# state_indicator.net
KiCad netlist of a schematic drawn in Altium Designer
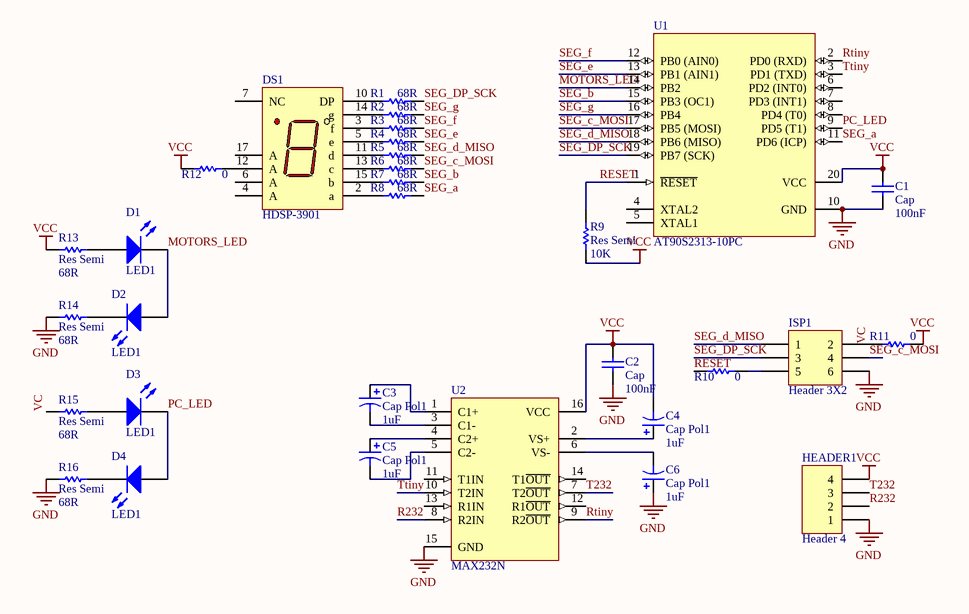
[diagram p0: state indicator.SchDoc]

(export (version "E")
  (design (tool "Eeschema 10.0.6"))
  (components
    (comp (ref "C1")
      (value "Cap")
      (footprint "CAPR5.08-7.8x3.2")
      (description "Capacitor")
      (fields (field (name "ALTIUM_VALUE") "100nF") (field (name "PUBLISHER") "Altium Limited"))
      (libsource (lib "Miscellaneous Devices") (part "Cap"))
    )
    (comp (ref "C2")
      (value "Cap")
      (footprint "CAPR5.08-7.8x3.2")
      (description "Capacitor")
      (fields (field (name "ALTIUM_VALUE") "100nF") (field (name "PUBLISHER") "Altium Limited"))
      (libsource (lib "Miscellaneous Devices") (part "Cap"))
    )
    (comp (ref "C3")
      (value "Cap Pol1")
      (footprint "CAPPR2-5x6.8")
      (description "Polarized Capacitor (Radial)")
      (fields (field (name "ALTIUM_VALUE") "1uF") (field (name "PUBLISHER") "Altium Limited"))
      (libsource (lib "state indicator") (part "Cap Pol1"))
    )
    (comp (ref "C4")
      (value "Cap Pol1")
      (footprint "CAPPR2-5x6.8")
      (description "Polarized Capacitor (Radial)")
      (fields (field (name "ALTIUM_VALUE") "1uF") (field (name "PUBLISHER") "Altium Limited"))
      (libsource (lib "state indicator") (part "Cap Pol1"))
    )
    (comp (ref "C5")
      (value "Cap Pol1")
      (footprint "CAPPR2-5x6.8")
      (description "Polarized Capacitor (Radial)")
      (fields (field (name "ALTIUM_VALUE") "1uF") (field (name "PUBLISHER") "Altium Limited"))
      (libsource (lib "state indicator") (part "Cap Pol1"))
    )
    (comp (ref "C6")
      (value "Cap Pol1")
      (footprint "CAPPR2-5x6.8")
      (description "Polarized Capacitor (Radial)")
      (fields (field (name "ALTIUM_VALUE") "1uF") (field (name "PUBLISHER") "Altium Limited"))
      (libsource (lib "state indicator") (part "Cap Pol1"))
    )
    (comp (ref "D1")
      (value "LED1")
      (footprint "LED-1")
      (description "Typical RED GaAs LED")
      (fields (field (name "PUBLISHER") "Altium Limited"))
      (libsource (lib "Miscellaneous Devices") (part "LED1"))
    )
    (comp (ref "D2")
      (value "LED1")
      (footprint "LED-1")
      (description "Typical RED GaAs LED")
      (fields (field (name "PUBLISHER") "Altium Limited"))
      (libsource (lib "Miscellaneous Devices") (part "LED1"))
    )
    (comp (ref "D3")
      (value "LED1")
      (footprint "LED-1")
      (description "Typical RED GaAs LED")
      (fields (field (name "PUBLISHER") "Altium Limited"))
      (libsource (lib "Miscellaneous Devices") (part "LED1"))
    )
    (comp (ref "D4")
      (value "LED1")
      (footprint "LED-1")
      (description "Typical RED GaAs LED")
      (fields (field (name "PUBLISHER") "Altium Limited"))
      (libsource (lib "Miscellaneous Devices") (part "LED1"))
    )
    (comp (ref "DS1")
      (value "HDSP-3901")
      (footprint "N-13")
      (description "20.32 mm Gray Package HER 7-Segment Display: CA, RH DP")
      (fields (field (name "PUBLISHER") "Altium Limited"))
      (libsource (lib "Agilent LED Display 7-Segment, 1-Digit") (part "HDSP-3901"))
    )
    (comp (ref "HEADER1")
      (value "Header 4")
      (footprint "HDR1X4")
      (description "Header, 4-Pin")
      (fields (field (name "PUBLISHER") "Altium Limited"))
      (libsource (lib "stabilizer") (part "Header 4"))
    )
    (comp (ref "ISP1")
      (value "Header 3X2")
      (footprint "stabilizer:HDR2X3")
      (description "Header, 3-Pin, Dual row")
      (fields (field (name "PUBLISHER") "Altium Limited"))
      (libsource (lib "Miscellaneous Connectors") (part "Header 3X2"))
    )
    (comp (ref "R1")
      (value "68R")
      (footprint "RES10-7.8X2.8")
      (description "Semiconductor Resistor")
      (fields (field (name "Comment") "es Semi") (field (name "PUBLISHER") "Altium Limited"))
      (libsource (lib "state indicator") (part "Res Semi"))
    )
    (comp (ref "R2")
      (value "68R")
      (footprint "RES10-7.8X2.8")
      (description "Semiconductor Resistor")
      (fields (field (name "Comment") "Res Semi") (field (name "PUBLISHER") "Altium Limited"))
      (libsource (lib "state indicator") (part "Res Semi"))
    )
    (comp (ref "R3")
      (value "68R")
      (footprint "RES10-7.8X2.8")
      (description "Semiconductor Resistor")
      (fields (field (name "Comment") "Res Semi") (field (name "PUBLISHER") "Altium Limited"))
      (libsource (lib "state indicator") (part "Res Semi"))
    )
    (comp (ref "R4")
      (value "68R")
      (footprint "RES10-7.8X2.8")
      (description "Semiconductor Resistor")
      (fields (field (name "Comment") "Res Semi") (field (name "PUBLISHER") "Altium Limited"))
      (libsource (lib "state indicator") (part "Res Semi"))
    )
    (comp (ref "R5")
      (value "68R")
      (footprint "RES10-7.8X2.8")
      (description "Semiconductor Resistor")
      (fields (field (name "Comment") "Res Semi") (field (name "PUBLISHER") "Altium Limited"))
      (libsource (lib "state indicator") (part "Res Semi"))
    )
    (comp (ref "R6")
      (value "68R")
      (footprint "RES10-7.8X2.8")
      (description "Semiconductor Resistor")
      (fields (field (name "Comment") "Res Semi") (field (name "PUBLISHER") "Altium Limited"))
      (libsource (lib "state indicator") (part "Res Semi"))
    )
    (comp (ref "R7")
      (value "68R")
      (footprint "RES10-7.8X2.8")
      (description "Semiconductor Resistor")
      (fields (field (name "Comment") "Res Semi") (field (name "PUBLISHER") "Altium Limited"))
      (libsource (lib "state indicator") (part "Res Semi"))
    )
    (comp (ref "R8")
      (value "68R")
      (footprint "RES10-7.8X2.8")
      (description "Semiconductor Resistor")
      (fields (field (name "Comment") "Res Semi") (field (name "PUBLISHER") "Altium Limited"))
      (libsource (lib "state indicator") (part "Res Semi"))
    )
    (comp (ref "R9")
      (value "Res Semi")
      (footprint "RES10-7.8X2.8")
      (description "Semiconductor Resistor")
      (fields (field (name "ALTIUM_VALUE") "10K") (field (name "PUBLISHER") "Altium Limited"))
      (libsource (lib "Miscellaneous Devices") (part "Res Semi"))
    )
    (comp (ref "R10")
      (value "0")
      (footprint "state indicator:RES10-7.8X2.8")
      (description "Semiconductor Resistor")
      (fields (field (name "Comment") "Res Semi") (field (name "PUBLISHER") "Altium Limited"))
      (libsource (lib "state indicator") (part "Res Semi"))
    )
    (comp (ref "R11")
      (value "0")
      (footprint "state indicator:RES10-7.8X2.8")
      (description "Semiconductor Resistor")
      (fields (field (name "Comment") "Res Semi") (field (name "PUBLISHER") "Altium Limited"))
      (libsource (lib "state indicator") (part "Res Semi"))
    )
    (comp (ref "R12")
      (value "0")
      (footprint "state indicator:RES10-7.8X2.8")
      (description "Semiconductor Resistor")
      (fields (field (name "Comment") "Res Semi") (field (name "PUBLISHER") "Altium Limited"))
      (libsource (lib "state indicator") (part "Res Semi"))
    )
    (comp (ref "R13")
      (value "Res Semi")
      (footprint "state indicator:RES10-7.8X2.8")
      (description "Semiconductor Resistor")
      (fields (field (name "ALTIUM_VALUE") "68R") (field (name "PUBLISHER") "Altium Limited"))
      (libsource (lib "state indicator") (part "Res Semi"))
    )
    (comp (ref "R14")
      (value "Res Semi")
      (footprint "state indicator:RES10-7.8X2.8")
      (description "Semiconductor Resistor")
      (fields (field (name "ALTIUM_VALUE") "68R") (field (name "PUBLISHER") "Altium Limited"))
      (libsource (lib "state indicator") (part "Res Semi"))
    )
    (comp (ref "R15")
      (value "Res Semi")
      (footprint "state indicator:RES10-7.8X2.8")
      (description "Semiconductor Resistor")
      (fields (field (name "ALTIUM_VALUE") "68R") (field (name "PUBLISHER") "Altium Limited"))
      (libsource (lib "state indicator") (part "Res Semi"))
    )
    (comp (ref "R16")
      (value "Res Semi")
      (footprint "state indicator:RES10-7.8X2.8")
      (description "Semiconductor Resistor")
      (fields (field (name "ALTIUM_VALUE") "68R") (field (name "PUBLISHER") "Altium Limited"))
      (libsource (lib "state indicator") (part "Res Semi"))
    )
    (comp (ref "U1")
      (value "AT90S2313-10PC")
      (footprint "DIP-20/D32.6")
      (description "8-Bit AVR Microcontroller with 2K Bytes of In-System Programmable Flash Memory")
      (fields (field (name "PUBLISHER") "Altium Limited"))
      (libsource (lib "stabilizer") (part "AT90S2313-10PC"))
    )
    (comp (ref "U2")
      (value "MAX232N")
      (footprint "N016")
      (description "Dual EIA-232 Driver/Receiver")
      (fields (field (name "PUBLISHER") "Altium Limited"))
      (libsource (lib "TI Interface Line Transceiver") (part "MAX232N"))
    )
  )
  (nets
    (net (code "1") (name "/MOTORS_LED") (class "Default")
      (node (ref "D1") (pin "2") (pinfunction "K_2") (pintype "passive"))
      (node (ref "D2") (pin "1") (pinfunction "A_1") (pintype "passive"))
      (node (ref "U1") (pin "14") (pinfunction "PB2_14") (pintype "bidirectional"))
    )
    (net (code "2") (name "/PC_LED") (class "Default")
      (node (ref "D3") (pin "2") (pinfunction "K_2") (pintype "passive"))
      (node (ref "D4") (pin "1") (pinfunction "A_1") (pintype "passive"))
      (node (ref "U1") (pin "9") (pinfunction "PD5_(T1)_9") (pintype "bidirectional"))
    )
    (net (code "3") (name "/R232") (class "Default")
      (node (ref "HEADER1") (pin "2") (pinfunction "2_2") (pintype "passive"))
      (node (ref "U2") (pin "8") (pinfunction "R2IN_8") (pintype "input"))
    )
    (net (code "4") (name "/RESET") (class "Default")
      (node (ref "R10") (pin "1") (pinfunction "1_1") (pintype "passive"))
      (node (ref "R9") (pin "2") (pinfunction "2_2") (pintype "passive"))
      (node (ref "U1") (pin "1") (pinfunction "~{RESET}_1") (pintype "input"))
    )
    (net (code "5") (name "/Rtiny") (class "Default")
      (node (ref "U1") (pin "2") (pinfunction "PD0_(RXD)_2") (pintype "bidirectional"))
      (node (ref "U2") (pin "9") (pinfunction "R2~{OUT}_9") (pintype "output"))
    )
    (net (code "6") (name "/SEG_DP_SCK") (class "Default")
      (node (ref "ISP1") (pin "3") (pinfunction "3_3") (pintype "passive"))
      (node (ref "R1") (pin "2") (pinfunction "2_2") (pintype "passive"))
      (node (ref "U1") (pin "19") (pinfunction "PB7_(SCK)_19") (pintype "bidirectional"))
    )
    (net (code "7") (name "/SEG_a") (class "Default")
      (node (ref "R8") (pin "2") (pinfunction "2_2") (pintype "passive"))
      (node (ref "U1") (pin "11") (pinfunction "PD6_(ICP)_11") (pintype "bidirectional"))
    )
    (net (code "8") (name "/SEG_b") (class "Default")
      (node (ref "R7") (pin "2") (pinfunction "2_2") (pintype "passive"))
      (node (ref "U1") (pin "15") (pinfunction "PB3_(OC1)_15") (pintype "bidirectional"))
    )
    (net (code "9") (name "/SEG_c_MOSI") (class "Default")
      (node (ref "ISP1") (pin "4") (pinfunction "4_4") (pintype "passive"))
      (node (ref "R6") (pin "2") (pinfunction "2_2") (pintype "passive"))
      (node (ref "U1") (pin "17") (pinfunction "PB5_(MOSI)_17") (pintype "bidirectional"))
    )
    (net (code "10") (name "/SEG_d_MISO") (class "Default")
      (node (ref "ISP1") (pin "1") (pinfunction "1_1") (pintype "passive"))
      (node (ref "R5") (pin "2") (pinfunction "2_2") (pintype "passive"))
      (node (ref "U1") (pin "18") (pinfunction "PB6_(MISO)_18") (pintype "bidirectional"))
    )
    (net (code "11") (name "/SEG_e") (class "Default")
      (node (ref "R4") (pin "2") (pinfunction "2_2") (pintype "passive"))
      (node (ref "U1") (pin "13") (pinfunction "PB1_(AIN1)_13") (pintype "bidirectional"))
    )
    (net (code "12") (name "/SEG_f") (class "Default")
      (node (ref "R3") (pin "2") (pinfunction "2_2") (pintype "passive"))
      (node (ref "U1") (pin "12") (pinfunction "PB0_(AIN0)_12") (pintype "bidirectional"))
    )
    (net (code "13") (name "/SEG_g") (class "Default")
      (node (ref "R2") (pin "2") (pinfunction "2_2") (pintype "passive"))
      (node (ref "U1") (pin "16") (pinfunction "PB4_16") (pintype "bidirectional"))
    )
    (net (code "14") (name "/T232") (class "Default")
      (node (ref "HEADER1") (pin "3") (pinfunction "3_3") (pintype "passive"))
      (node (ref "U2") (pin "7") (pinfunction "T2~{OUT}_7") (pintype "output"))
    )
    (net (code "15") (name "/Ttiny") (class "Default")
      (node (ref "U1") (pin "3") (pinfunction "PD1_(TXD)_3") (pintype "bidirectional"))
      (node (ref "U2") (pin "10") (pinfunction "T2IN_10") (pintype "input"))
    )
    (net (code "16") (name "/VC") (class "Default")
      (node (ref "ISP1") (pin "2") (pinfunction "2_2") (pintype "passive"))
      (node (ref "R11") (pin "1") (pinfunction "1_1") (pintype "passive"))
      (node (ref "R15") (pin "1") (pinfunction "1_1") (pintype "passive"))
    )
    (net (code "17") (name "GND") (class "Default")
      (node (ref "C1") (pin "2") (pinfunction "2_2") (pintype "passive"))
      (node (ref "C2") (pin "2") (pinfunction "2_2") (pintype "passive"))
      (node (ref "C6") (pin "1") (pinfunction "1_1") (pintype "passive"))
      (node (ref "HEADER1") (pin "1") (pinfunction "1_1") (pintype "passive"))
      (node (ref "ISP1") (pin "6") (pinfunction "6_6") (pintype "passive"))
      (node (ref "R14") (pin "1") (pinfunction "1_1") (pintype "passive"))
      (node (ref "R16") (pin "1") (pinfunction "1_1") (pintype "passive"))
      (node (ref "U1") (pin "10") (pinfunction "GND_10") (pintype "power_in"))
      (node (ref "U2") (pin "15") (pinfunction "GND_15") (pintype "power_in"))
    )
    (net (code "18") (name "Net-(D1-A)") (class "Default")
      (node (ref "D1") (pin "1") (pinfunction "A_1") (pintype "passive"))
      (node (ref "R13") (pin "2") (pinfunction "2_2") (pintype "passive"))
    )
    (net (code "19") (name "Net-(D2-K)") (class "Default")
      (node (ref "D2") (pin "2") (pinfunction "K_2") (pintype "passive"))
      (node (ref "R14") (pin "2") (pinfunction "2_2") (pintype "passive"))
    )
    (net (code "20") (name "Net-(D3-A)") (class "Default")
      (node (ref "D3") (pin "1") (pinfunction "A_1") (pintype "passive"))
      (node (ref "R15") (pin "2") (pinfunction "2_2") (pintype "passive"))
    )
    (net (code "21") (name "Net-(D4-K)") (class "Default")
      (node (ref "D4") (pin "2") (pinfunction "K_2") (pintype "passive"))
      (node (ref "R16") (pin "2") (pinfunction "2_2") (pintype "passive"))
    )
    (net (code "22") (name "Net-(DS1-A-Pad12)") (class "Default")
      (node (ref "DS1") (pin "12") (pinfunction "A_12") (pintype "passive"))
      (node (ref "R12") (pin "2") (pinfunction "2_2") (pintype "passive"))
    )
    (net (code "23") (name "Net-(DS1-DP)") (class "Default")
      (node (ref "DS1") (pin "10") (pinfunction "DP_10") (pintype "passive"))
      (node (ref "R1") (pin "1") (pinfunction "1_1") (pintype "passive"))
    )
    (net (code "24") (name "Net-(DS1-a)") (class "Default")
      (node (ref "DS1") (pin "2") (pinfunction "a_2") (pintype "passive"))
      (node (ref "R8") (pin "1") (pinfunction "1_1") (pintype "passive"))
    )
    (net (code "25") (name "Net-(DS1-b)") (class "Default")
      (node (ref "DS1") (pin "15") (pinfunction "b_15") (pintype "passive"))
      (node (ref "R7") (pin "1") (pinfunction "1_1") (pintype "passive"))
    )
    (net (code "26") (name "Net-(DS1-c)") (class "Default")
      (node (ref "DS1") (pin "13") (pinfunction "c_13") (pintype "passive"))
      (node (ref "R6") (pin "1") (pinfunction "1_1") (pintype "passive"))
    )
    (net (code "27") (name "Net-(DS1-d)") (class "Default")
      (node (ref "DS1") (pin "11") (pinfunction "d_11") (pintype "passive"))
      (node (ref "R5") (pin "1") (pinfunction "1_1") (pintype "passive"))
    )
    (net (code "28") (name "Net-(DS1-e)") (class "Default")
      (node (ref "DS1") (pin "5") (pinfunction "e_5") (pintype "passive"))
      (node (ref "R4") (pin "1") (pinfunction "1_1") (pintype "passive"))
    )
    (net (code "29") (name "Net-(DS1-f)") (class "Default")
      (node (ref "DS1") (pin "3") (pinfunction "f_3") (pintype "passive"))
      (node (ref "R3") (pin "1") (pinfunction "1_1") (pintype "passive"))
    )
    (net (code "30") (name "Net-(DS1-g)") (class "Default")
      (node (ref "DS1") (pin "14") (pinfunction "g_14") (pintype "passive"))
      (node (ref "R2") (pin "1") (pinfunction "1_1") (pintype "passive"))
    )
    (net (code "31") (name "Net-(ISP1-Pad5)") (class "Default")
      (node (ref "ISP1") (pin "5") (pinfunction "5_5") (pintype "passive"))
      (node (ref "R10") (pin "2") (pinfunction "2_2") (pintype "passive"))
    )
    (net (code "32") (name "Net-(U2-C1+)") (class "Default")
      (node (ref "C3") (pin "1") (pinfunction "1_1") (pintype "passive"))
      (node (ref "U2") (pin "1") (pinfunction "C1+_1") (pintype "passive"))
    )
    (net (code "33") (name "Net-(U2-C1-)") (class "Default")
      (node (ref "C3") (pin "2") (pinfunction "2_2") (pintype "passive"))
      (node (ref "U2") (pin "3") (pinfunction "C1-_3") (pintype "passive"))
    )
    (net (code "34") (name "Net-(U2-C2+)") (class "Default")
      (node (ref "C5") (pin "1") (pinfunction "1_1") (pintype "passive"))
      (node (ref "U2") (pin "4") (pinfunction "C2+_4") (pintype "passive"))
    )
    (net (code "35") (name "Net-(U2-C2-)") (class "Default")
      (node (ref "C5") (pin "2") (pinfunction "2_2") (pintype "passive"))
      (node (ref "U2") (pin "5") (pinfunction "C2-_5") (pintype "passive"))
    )
    (net (code "36") (name "Net-(U2-VS+)") (class "Default")
      (node (ref "C4") (pin "1") (pinfunction "1_1") (pintype "passive"))
      (node (ref "U2") (pin "2") (pinfunction "VS+_2") (pintype "power_in"))
    )
    (net (code "37") (name "Net-(U2-VS-)") (class "Default")
      (node (ref "C6") (pin "2") (pinfunction "2_2") (pintype "passive"))
      (node (ref "U2") (pin "6") (pinfunction "VS-_6") (pintype "power_in"))
    )
    (net (code "38") (name "VCC") (class "Default")
      (node (ref "C1") (pin "1") (pinfunction "1_1") (pintype "passive"))
      (node (ref "C2") (pin "1") (pinfunction "1_1") (pintype "passive"))
      (node (ref "C4") (pin "2") (pinfunction "2_2") (pintype "passive"))
      (node (ref "HEADER1") (pin "4") (pinfunction "4_4") (pintype "passive"))
      (node (ref "R11") (pin "2") (pinfunction "2_2") (pintype "passive"))
      (node (ref "R12") (pin "1") (pinfunction "1_1") (pintype "passive"))
      (node (ref "R13") (pin "1") (pinfunction "1_1") (pintype "passive"))
      (node (ref "R9") (pin "1") (pinfunction "1_1") (pintype "passive"))
      (node (ref "U1") (pin "20") (pinfunction "VCC_20") (pintype "power_in"))
      (node (ref "U2") (pin "16") (pinfunction "VCC_16") (pintype "power_in"))
    )
    (net (code "39") (name "unconnected-(DS1-A-Pad4)") (class "Default")
      (node (ref "DS1") (pin "4") (pinfunction "A_4") (pintype "passive"))
    )
    (net (code "40") (name "unconnected-(DS1-A-Pad6)") (class "Default")
      (node (ref "DS1") (pin "6") (pinfunction "A_6") (pintype "passive"))
    )
    (net (code "41") (name "unconnected-(DS1-A-Pad17)") (class "Default")
      (node (ref "DS1") (pin "17") (pinfunction "A_17") (pintype "passive"))
    )
    (net (code "42") (name "unconnected-(DS1-NC-Pad7)") (class "Default")
      (node (ref "DS1") (pin "7") (pinfunction "NC_7") (pintype "passive"))
    )
    (net (code "43") (name "unconnected-(U1-PD2_(INT0)-Pad6)") (class "Default")
      (node (ref "U1") (pin "6") (pinfunction "PD2_(INT0)_6") (pintype "bidirectional"))
    )
    (net (code "44") (name "unconnected-(U1-PD3_(INT1)-Pad7)") (class "Default")
      (node (ref "U1") (pin "7") (pinfunction "PD3_(INT1)_7") (pintype "bidirectional"))
    )
    (net (code "45") (name "unconnected-(U1-PD4_(T0)-Pad8)") (class "Default")
      (node (ref "U1") (pin "8") (pinfunction "PD4_(T0)_8") (pintype "bidirectional"))
    )
    (net (code "46") (name "unconnected-(U1-XTAL1-Pad5)") (class "Default")
      (node (ref "U1") (pin "5") (pinfunction "XTAL1_5") (pintype "passive"))
    )
    (net (code "47") (name "unconnected-(U1-XTAL2-Pad4)") (class "Default")
      (node (ref "U1") (pin "4") (pinfunction "XTAL2_4") (pintype "passive"))
    )
    (net (code "48") (name "unconnected-(U2-R1IN-Pad13)") (class "Default")
      (node (ref "U2") (pin "13") (pinfunction "R1IN_13") (pintype "input"))
    )
    (net (code "49") (name "unconnected-(U2-R1~{OUT}-Pad12)") (class "Default")
      (node (ref "U2") (pin "12") (pinfunction "R1~{OUT}_12") (pintype "output"))
    )
    (net (code "50") (name "unconnected-(U2-T1IN-Pad11)") (class "Default")
      (node (ref "U2") (pin "11") (pinfunction "T1IN_11") (pintype "input"))
    )
    (net (code "51") (name "unconnected-(U2-T1~{OUT}-Pad14)") (class "Default")
      (node (ref "U2") (pin "14") (pinfunction "T1~{OUT}_14") (pintype "output"))
    )
  )
)
